# ProPrj_Climate_Monitoring_2025-02-02.net
KiCad netlist of a schematic drawn in EasyEDA Pro
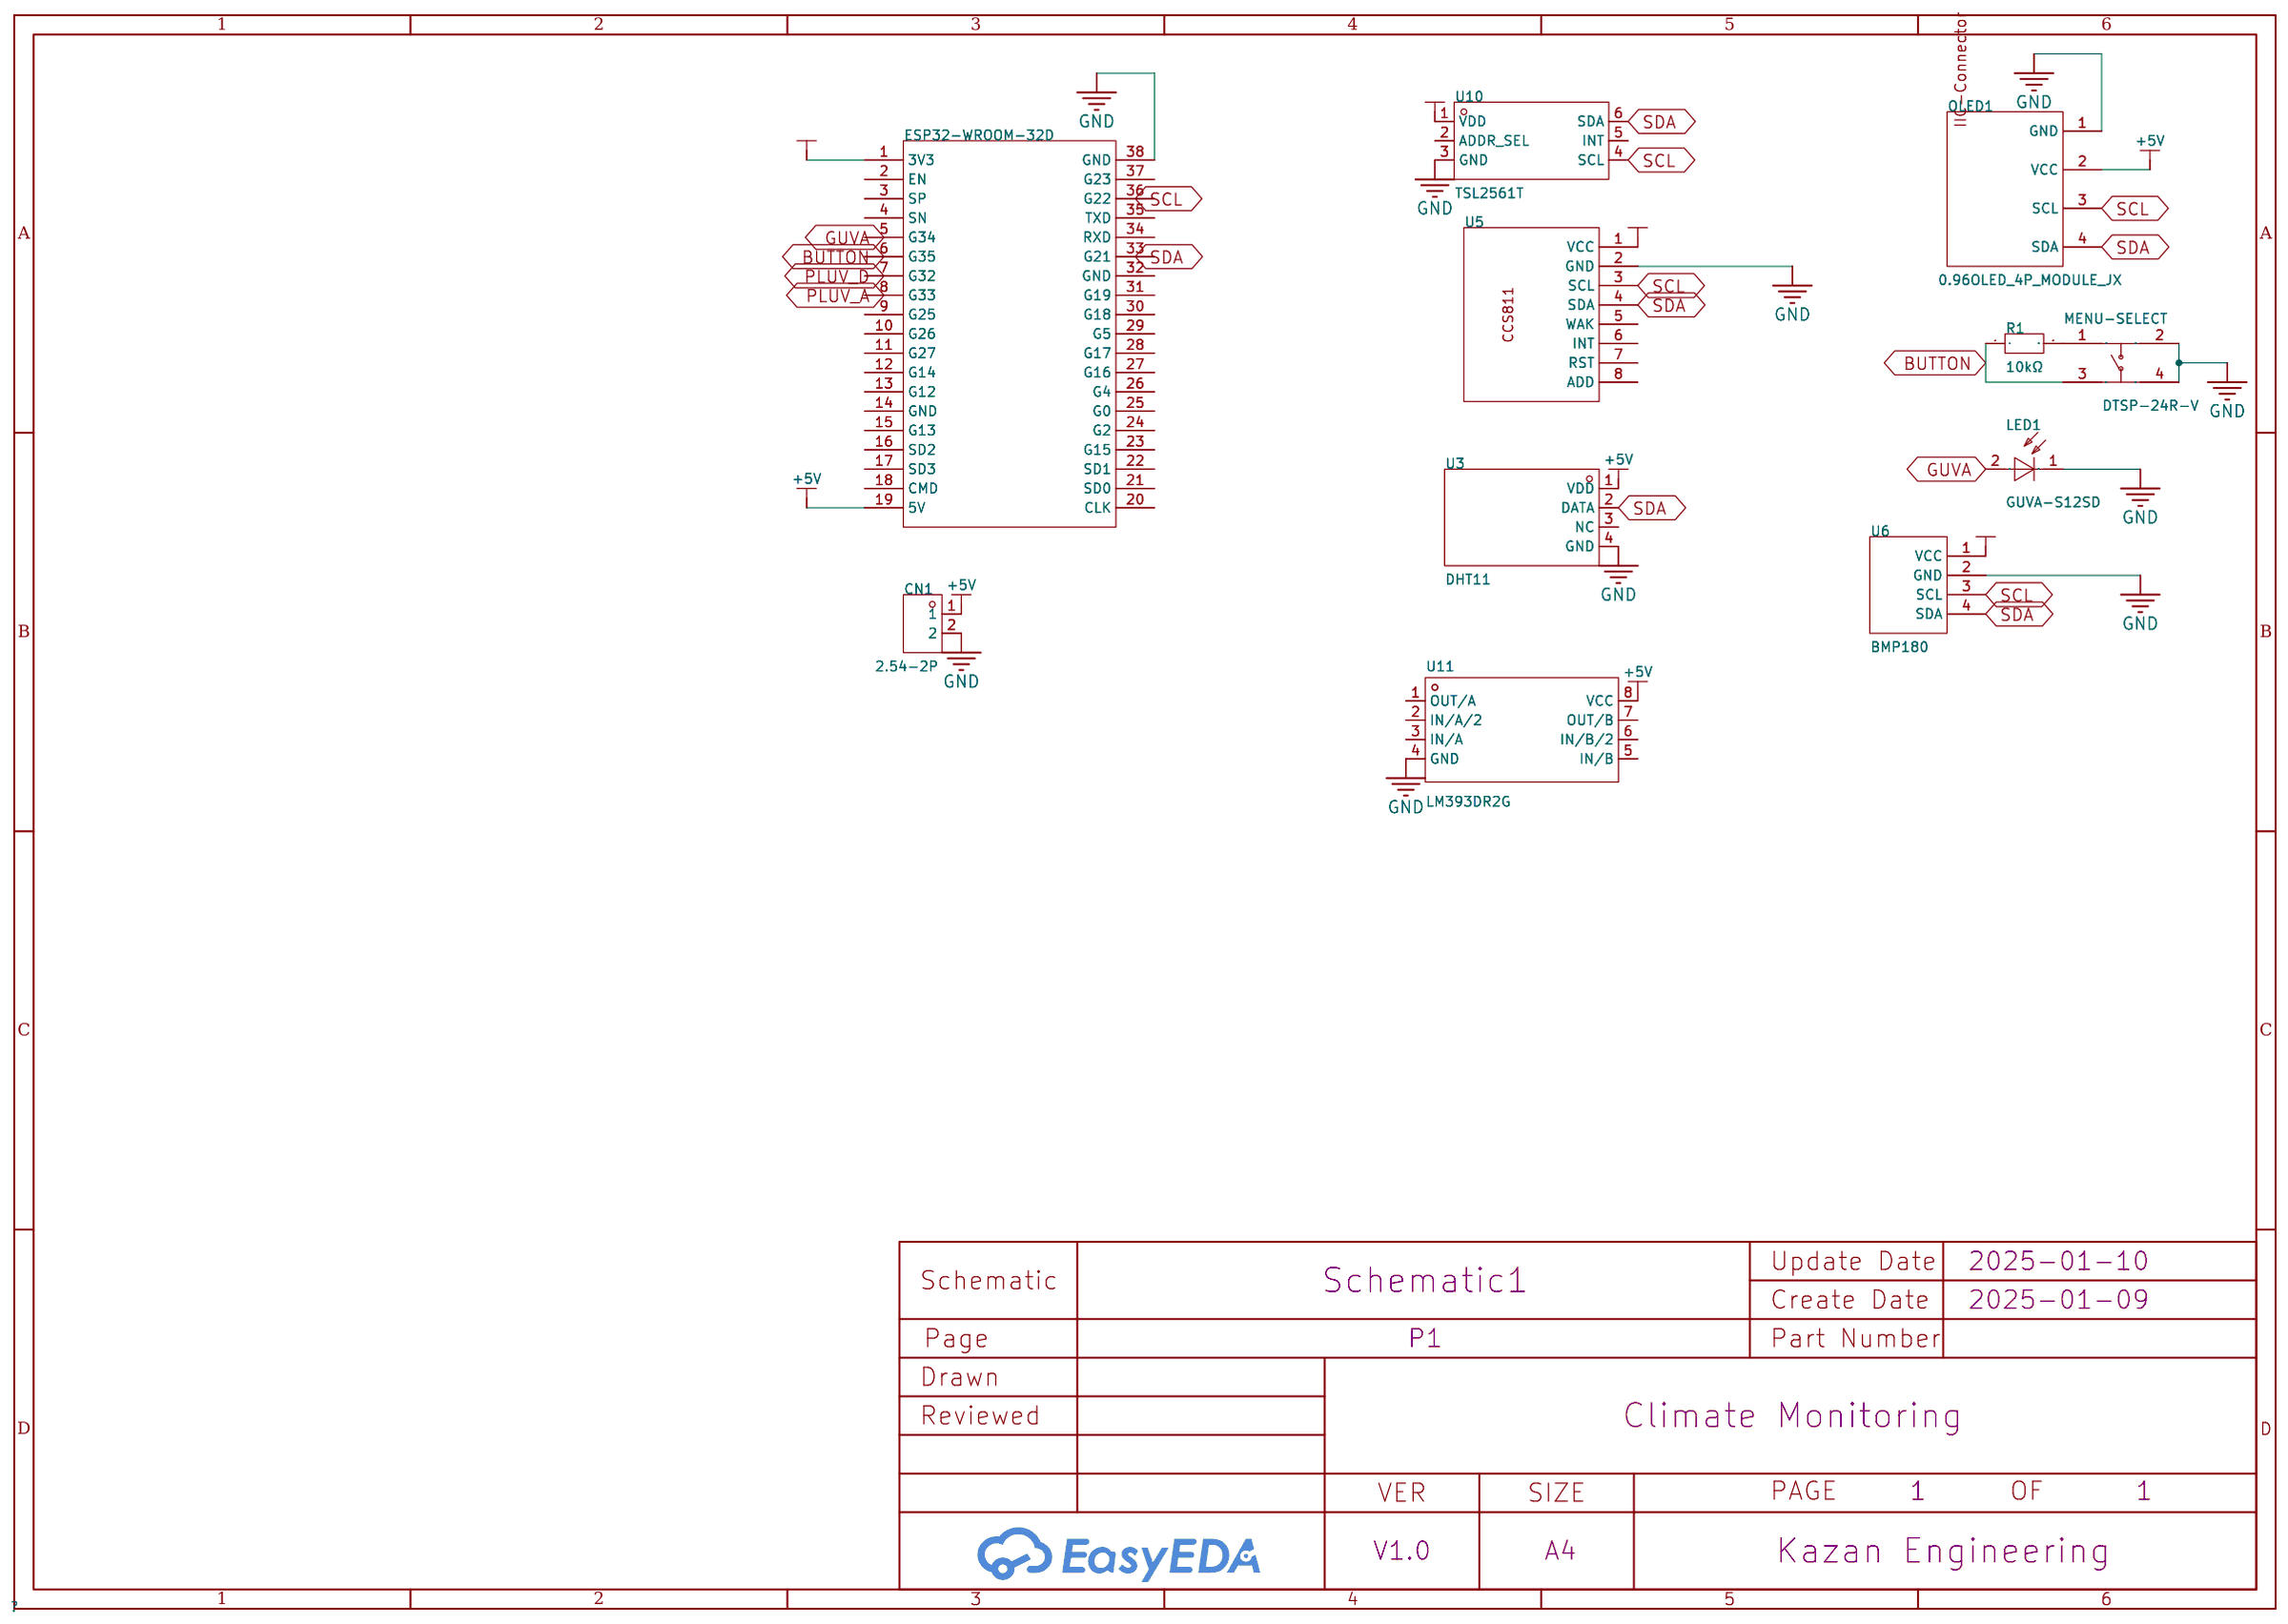
[diagram p0: schematic sheet]

(export (version "E")
  (design (tool "Eeschema 10.0.6"))
  (components
    (comp (ref "CN1")
      (value "2.54-2P")
      (footprint "easyedapro:CONN-TH_2P-P2.54_C9900022459")
      (libsource (lib "easyedapro") (part "2.54-2P"))
    )
    (comp (ref "ESP32-WROOM-32D")
      (value "~")
      (footprint "easyedapro:esp32_38p")
      (libsource (lib "easyedapro") (part "ESP32_38p開發板"))
    )
    (comp (ref "LED1")
      (value "GUVA-S12SD")
      (footprint "easyedapro:LED-SMD_L3.2-W2.8-RD")
      (fields (field (name "Manufacturer") "Genicom"))
      (libsource (lib "easyedapro") (part "GUVA-S12SD"))
    )
    (comp (ref "MENU-SELECT")
      (value "DTSP-24R-V")
      (footprint "easyedapro:SW-TH_4P-L12.0-W12.0-P5.00-LS13.0-EH")
      (libsource (lib "easyedapro") (part "DTSP-24R-V"))
    )
    (comp (ref "OLED1")
      (value "0.96OLED_4P_MODULE_JX")
      (footprint "easyedapro:0.96OLED_4P")
      (libsource (lib "easyedapro") (part "0.96OLED_4P_MODULE_JX"))
    )
    (comp (ref "R1")
      (value "10kΩ")
      (footprint "easyedapro:RES-TH_BD2.5-L6.5-P10.50-D0.6")
      (fields
        (field (name "Manufacturer Part") "PR01000101002JR500")
        (field (name "Manufacturer") "VISHAY(威世)")
      )
      (libsource (lib "easyedapro") (part "PR01000101002JR500"))
    )
    (comp (ref "U3")
      (value "DHT11")
      (footprint "easyedapro:SENSOR-TH_DHT11")
      (fields (field (name "Manufacturer") "广州奥松"))
      (libsource (lib "easyedapro") (part "DHT11"))
    )
    (comp (ref "U5")
      (value "~")
      (footprint "easyedapro:CCS811")
      (libsource (lib "easyedapro") (part "CCS811"))
    )
    (comp (ref "U6")
      (value "BMP180")
      (footprint "easyedapro:BMP-180")
      (libsource (lib "easyedapro") (part "BMP180"))
    )
    (comp (ref "U10")
      (value "TSL2561T")
      (footprint "easyedapro:TMP-6_L3.8-W1.6-P0.90-BL")
      (fields (field (name "Manufacturer") "ams(艾迈斯半导体)"))
      (libsource (lib "easyedapro") (part "TSL2561T"))
    )
    (comp (ref "U11")
      (value "LM393DR2G")
      (footprint "easyedapro:SOIC-8_L5.0-W4.0-P1.27-LS6.0-BL")
      (fields (field (name "Manufacturer") "onsemi(安森美)"))
      (libsource (lib "easyedapro") (part "LM393DR2G"))
    )
  )
  (nets
    (net (code "1") (name "+3.3V") (class "Default")
      (node (ref "ESP32-WROOM-32D") (pin "1") (pinfunction "3V3_1") (pintype "input"))
      (node (ref "U10") (pin "1") (pinfunction "VDD_1") (pintype "unspecified"))
      (node (ref "U5") (pin "1") (pinfunction "VCC_1") (pintype "input"))
      (node (ref "U6") (pin "1") (pinfunction "VCC_1") (pintype "input"))
    )
    (net (code "2") (name "+5V") (class "Default")
      (node (ref "CN1") (pin "1") (pinfunction "1_1") (pintype "unspecified"))
      (node (ref "ESP32-WROOM-32D") (pin "19") (pinfunction "5V_19") (pintype "input"))
      (node (ref "OLED1") (pin "2") (pinfunction "VCC_2") (pintype "input"))
      (node (ref "U11") (pin "8") (pinfunction "VCC_8") (pintype "unspecified"))
      (node (ref "U3") (pin "1") (pinfunction "VDD_1") (pintype "unspecified"))
    )
    (net (code "3") (name "BUTTON") (class "Default")
      (node (ref "ESP32-WROOM-32D") (pin "6") (pinfunction "G35_6") (pintype "input"))
      (node (ref "MENU-SELECT") (pin "3") (pinfunction "3_3") (pintype "unspecified"))
      (node (ref "R1") (pin "1") (pinfunction "1_1") (pintype "unspecified"))
    )
    (net (code "4") (name "GND") (class "Default")
      (node (ref "CN1") (pin "2") (pinfunction "2_2") (pintype "unspecified"))
      (node (ref "ESP32-WROOM-32D") (pin "38") (pinfunction "GND_38") (pintype "input"))
      (node (ref "LED1") (pin "1") (pinfunction "C_1") (pintype "unspecified"))
      (node (ref "MENU-SELECT") (pin "2") (pinfunction "2_2") (pintype "unspecified"))
      (node (ref "MENU-SELECT") (pin "4") (pinfunction "4_4") (pintype "unspecified"))
      (node (ref "OLED1") (pin "1") (pinfunction "GND_1") (pintype "input"))
      (node (ref "U10") (pin "3") (pinfunction "GND_3") (pintype "unspecified"))
      (node (ref "U11") (pin "4") (pinfunction "GND_4") (pintype "unspecified"))
      (node (ref "U3") (pin "4") (pinfunction "GND_4") (pintype "unspecified"))
      (node (ref "U5") (pin "2") (pinfunction "GND_2") (pintype "input"))
      (node (ref "U6") (pin "2") (pinfunction "GND_2") (pintype "input"))
    )
    (net (code "5") (name "GUVA") (class "Default")
      (node (ref "ESP32-WROOM-32D") (pin "5") (pinfunction "G34_5") (pintype "input"))
      (node (ref "LED1") (pin "2") (pinfunction "A_2") (pintype "unspecified"))
    )
    (net (code "6") (name "Net-(MENU-SELECT-Pad1)") (class "Default")
      (node (ref "MENU-SELECT") (pin "1") (pinfunction "1_1") (pintype "unspecified"))
      (node (ref "R1") (pin "2") (pinfunction "2_2") (pintype "unspecified"))
    )
    (net (code "7") (name "PLUV_A") (class "Default")
      (node (ref "ESP32-WROOM-32D") (pin "8") (pinfunction "G33_8") (pintype "input"))
    )
    (net (code "8") (name "PLUV_D") (class "Default")
      (node (ref "ESP32-WROOM-32D") (pin "7") (pinfunction "G32_7") (pintype "input"))
    )
    (net (code "9") (name "SCL") (class "Default")
      (node (ref "ESP32-WROOM-32D") (pin "36") (pinfunction "G22_36") (pintype "input"))
      (node (ref "OLED1") (pin "3") (pinfunction "SCL_3") (pintype "input"))
      (node (ref "U10") (pin "4") (pinfunction "SCL_4") (pintype "unspecified"))
      (node (ref "U5") (pin "3") (pinfunction "SCL_3") (pintype "input"))
      (node (ref "U6") (pin "3") (pinfunction "SCL_3") (pintype "input"))
    )
    (net (code "10") (name "SDA") (class "Default")
      (node (ref "ESP32-WROOM-32D") (pin "33") (pinfunction "G21_33") (pintype "input"))
      (node (ref "OLED1") (pin "4") (pinfunction "SDA_4") (pintype "input"))
      (node (ref "U10") (pin "6") (pinfunction "SDA_6") (pintype "unspecified"))
      (node (ref "U3") (pin "2") (pinfunction "DATA_2") (pintype "unspecified"))
      (node (ref "U5") (pin "4") (pinfunction "SDA_4") (pintype "input"))
      (node (ref "U6") (pin "4") (pinfunction "SDA_4") (pintype "input"))
    )
    (net (code "11") (name "unconnected-(ESP32-WROOM-32D-CLK-Pad20)") (class "Default")
      (node (ref "ESP32-WROOM-32D") (pin "20") (pinfunction "CLK_20") (pintype "input"))
    )
    (net (code "12") (name "unconnected-(ESP32-WROOM-32D-CMD-Pad18)") (class "Default")
      (node (ref "ESP32-WROOM-32D") (pin "18") (pinfunction "CMD_18") (pintype "input"))
    )
    (net (code "13") (name "unconnected-(ESP32-WROOM-32D-EN-Pad2)") (class "Default")
      (node (ref "ESP32-WROOM-32D") (pin "2") (pinfunction "EN_2") (pintype "input"))
    )
    (net (code "14") (name "unconnected-(ESP32-WROOM-32D-G0-Pad25)") (class "Default")
      (node (ref "ESP32-WROOM-32D") (pin "25") (pinfunction "G0_25") (pintype "input"))
    )
    (net (code "15") (name "unconnected-(ESP32-WROOM-32D-G2-Pad24)") (class "Default")
      (node (ref "ESP32-WROOM-32D") (pin "24") (pinfunction "G2_24") (pintype "input"))
    )
    (net (code "16") (name "unconnected-(ESP32-WROOM-32D-G4-Pad26)") (class "Default")
      (node (ref "ESP32-WROOM-32D") (pin "26") (pinfunction "G4_26") (pintype "input"))
    )
    (net (code "17") (name "unconnected-(ESP32-WROOM-32D-G5-Pad29)") (class "Default")
      (node (ref "ESP32-WROOM-32D") (pin "29") (pinfunction "G5_29") (pintype "input"))
    )
    (net (code "18") (name "unconnected-(ESP32-WROOM-32D-G12-Pad13)") (class "Default")
      (node (ref "ESP32-WROOM-32D") (pin "13") (pinfunction "G12_13") (pintype "input"))
    )
    (net (code "19") (name "unconnected-(ESP32-WROOM-32D-G13-Pad15)") (class "Default")
      (node (ref "ESP32-WROOM-32D") (pin "15") (pinfunction "G13_15") (pintype "input"))
    )
    (net (code "20") (name "unconnected-(ESP32-WROOM-32D-G14-Pad12)") (class "Default")
      (node (ref "ESP32-WROOM-32D") (pin "12") (pinfunction "G14_12") (pintype "input"))
    )
    (net (code "21") (name "unconnected-(ESP32-WROOM-32D-G15-Pad23)") (class "Default")
      (node (ref "ESP32-WROOM-32D") (pin "23") (pinfunction "G15_23") (pintype "input"))
    )
    (net (code "22") (name "unconnected-(ESP32-WROOM-32D-G16-Pad27)") (class "Default")
      (node (ref "ESP32-WROOM-32D") (pin "27") (pinfunction "G16_27") (pintype "input"))
    )
    (net (code "23") (name "unconnected-(ESP32-WROOM-32D-G17-Pad28)") (class "Default")
      (node (ref "ESP32-WROOM-32D") (pin "28") (pinfunction "G17_28") (pintype "input"))
    )
    (net (code "24") (name "unconnected-(ESP32-WROOM-32D-G18-Pad30)") (class "Default")
      (node (ref "ESP32-WROOM-32D") (pin "30") (pinfunction "G18_30") (pintype "input"))
    )
    (net (code "25") (name "unconnected-(ESP32-WROOM-32D-G19-Pad31)") (class "Default")
      (node (ref "ESP32-WROOM-32D") (pin "31") (pinfunction "G19_31") (pintype "input"))
    )
    (net (code "26") (name "unconnected-(ESP32-WROOM-32D-G23-Pad37)") (class "Default")
      (node (ref "ESP32-WROOM-32D") (pin "37") (pinfunction "G23_37") (pintype "input"))
    )
    (net (code "27") (name "unconnected-(ESP32-WROOM-32D-G25-Pad9)") (class "Default")
      (node (ref "ESP32-WROOM-32D") (pin "9") (pinfunction "G25_9") (pintype "input"))
    )
    (net (code "28") (name "unconnected-(ESP32-WROOM-32D-G26-Pad10)") (class "Default")
      (node (ref "ESP32-WROOM-32D") (pin "10") (pinfunction "G26_10") (pintype "input"))
    )
    (net (code "29") (name "unconnected-(ESP32-WROOM-32D-G27-Pad11)") (class "Default")
      (node (ref "ESP32-WROOM-32D") (pin "11") (pinfunction "G27_11") (pintype "input"))
    )
    (net (code "30") (name "unconnected-(ESP32-WROOM-32D-GND-Pad14)") (class "Default")
      (node (ref "ESP32-WROOM-32D") (pin "14") (pinfunction "GND_14") (pintype "input"))
    )
    (net (code "31") (name "unconnected-(ESP32-WROOM-32D-GND-Pad32)") (class "Default")
      (node (ref "ESP32-WROOM-32D") (pin "32") (pinfunction "GND_32") (pintype "input"))
    )
    (net (code "32") (name "unconnected-(ESP32-WROOM-32D-RXD-Pad34)") (class "Default")
      (node (ref "ESP32-WROOM-32D") (pin "34") (pinfunction "RXD_34") (pintype "input"))
    )
    (net (code "33") (name "unconnected-(ESP32-WROOM-32D-SD0-Pad21)") (class "Default")
      (node (ref "ESP32-WROOM-32D") (pin "21") (pinfunction "SD0_21") (pintype "input"))
    )
    (net (code "34") (name "unconnected-(ESP32-WROOM-32D-SD1-Pad22)") (class "Default")
      (node (ref "ESP32-WROOM-32D") (pin "22") (pinfunction "SD1_22") (pintype "input"))
    )
    (net (code "35") (name "unconnected-(ESP32-WROOM-32D-SD2-Pad16)") (class "Default")
      (node (ref "ESP32-WROOM-32D") (pin "16") (pinfunction "SD2_16") (pintype "input"))
    )
    (net (code "36") (name "unconnected-(ESP32-WROOM-32D-SD3-Pad17)") (class "Default")
      (node (ref "ESP32-WROOM-32D") (pin "17") (pinfunction "SD3_17") (pintype "input"))
    )
    (net (code "37") (name "unconnected-(ESP32-WROOM-32D-SN-Pad4)") (class "Default")
      (node (ref "ESP32-WROOM-32D") (pin "4") (pinfunction "SN_4") (pintype "input"))
    )
    (net (code "38") (name "unconnected-(ESP32-WROOM-32D-SP-Pad3)") (class "Default")
      (node (ref "ESP32-WROOM-32D") (pin "3") (pinfunction "SP_3") (pintype "input"))
    )
    (net (code "39") (name "unconnected-(ESP32-WROOM-32D-TXD-Pad35)") (class "Default")
      (node (ref "ESP32-WROOM-32D") (pin "35") (pinfunction "TXD_35") (pintype "input"))
    )
    (net (code "40") (name "unconnected-(U3-NC-Pad3)") (class "Default")
      (node (ref "U3") (pin "3") (pinfunction "NC_3") (pintype "unspecified"))
    )
    (net (code "41") (name "unconnected-(U5-ADD-Pad8)") (class "Default")
      (node (ref "U5") (pin "8") (pinfunction "ADD_8") (pintype "input"))
    )
    (net (code "42") (name "unconnected-(U5-INT-Pad6)") (class "Default")
      (node (ref "U5") (pin "6") (pinfunction "INT_6") (pintype "input"))
    )
    (net (code "43") (name "unconnected-(U5-RST-Pad7)") (class "Default")
      (node (ref "U5") (pin "7") (pinfunction "RST_7") (pintype "input"))
    )
    (net (code "44") (name "unconnected-(U5-WAK-Pad5)") (class "Default")
      (node (ref "U5") (pin "5") (pinfunction "WAK_5") (pintype "input"))
    )
    (net (code "45") (name "unconnected-(U10-ADDR_SEL-Pad2)") (class "Default")
      (node (ref "U10") (pin "2") (pinfunction "ADDR_SEL_2") (pintype "unspecified"))
    )
    (net (code "46") (name "unconnected-(U10-INT-Pad5)") (class "Default")
      (node (ref "U10") (pin "5") (pinfunction "INT_5") (pintype "unspecified"))
    )
    (net (code "47") (name "unconnected-(U11-IN{slash}A-Pad3)") (class "Default")
      (node (ref "U11") (pin "3") (pinfunction "IN/A_3") (pintype "unspecified"))
    )
    (net (code "48") (name "unconnected-(U11-IN{slash}A{slash}2-Pad2)") (class "Default")
      (node (ref "U11") (pin "2") (pinfunction "IN/A/2_2") (pintype "unspecified"))
    )
    (net (code "49") (name "unconnected-(U11-IN{slash}B-Pad5)") (class "Default")
      (node (ref "U11") (pin "5") (pinfunction "IN/B_5") (pintype "unspecified"))
    )
    (net (code "50") (name "unconnected-(U11-IN{slash}B{slash}2-Pad6)") (class "Default")
      (node (ref "U11") (pin "6") (pinfunction "IN/B/2_6") (pintype "unspecified"))
    )
    (net (code "51") (name "unconnected-(U11-OUT{slash}A-Pad1)") (class "Default")
      (node (ref "U11") (pin "1") (pinfunction "OUT/A_1") (pintype "unspecified"))
    )
    (net (code "52") (name "unconnected-(U11-OUT{slash}B-Pad7)") (class "Default")
      (node (ref "U11") (pin "7") (pinfunction "OUT/B_7") (pintype "unspecified"))
    )
  )
)
